# 08_Level_conv_misc.net
KiCad netlist of a schematic drawn in Altium Designer
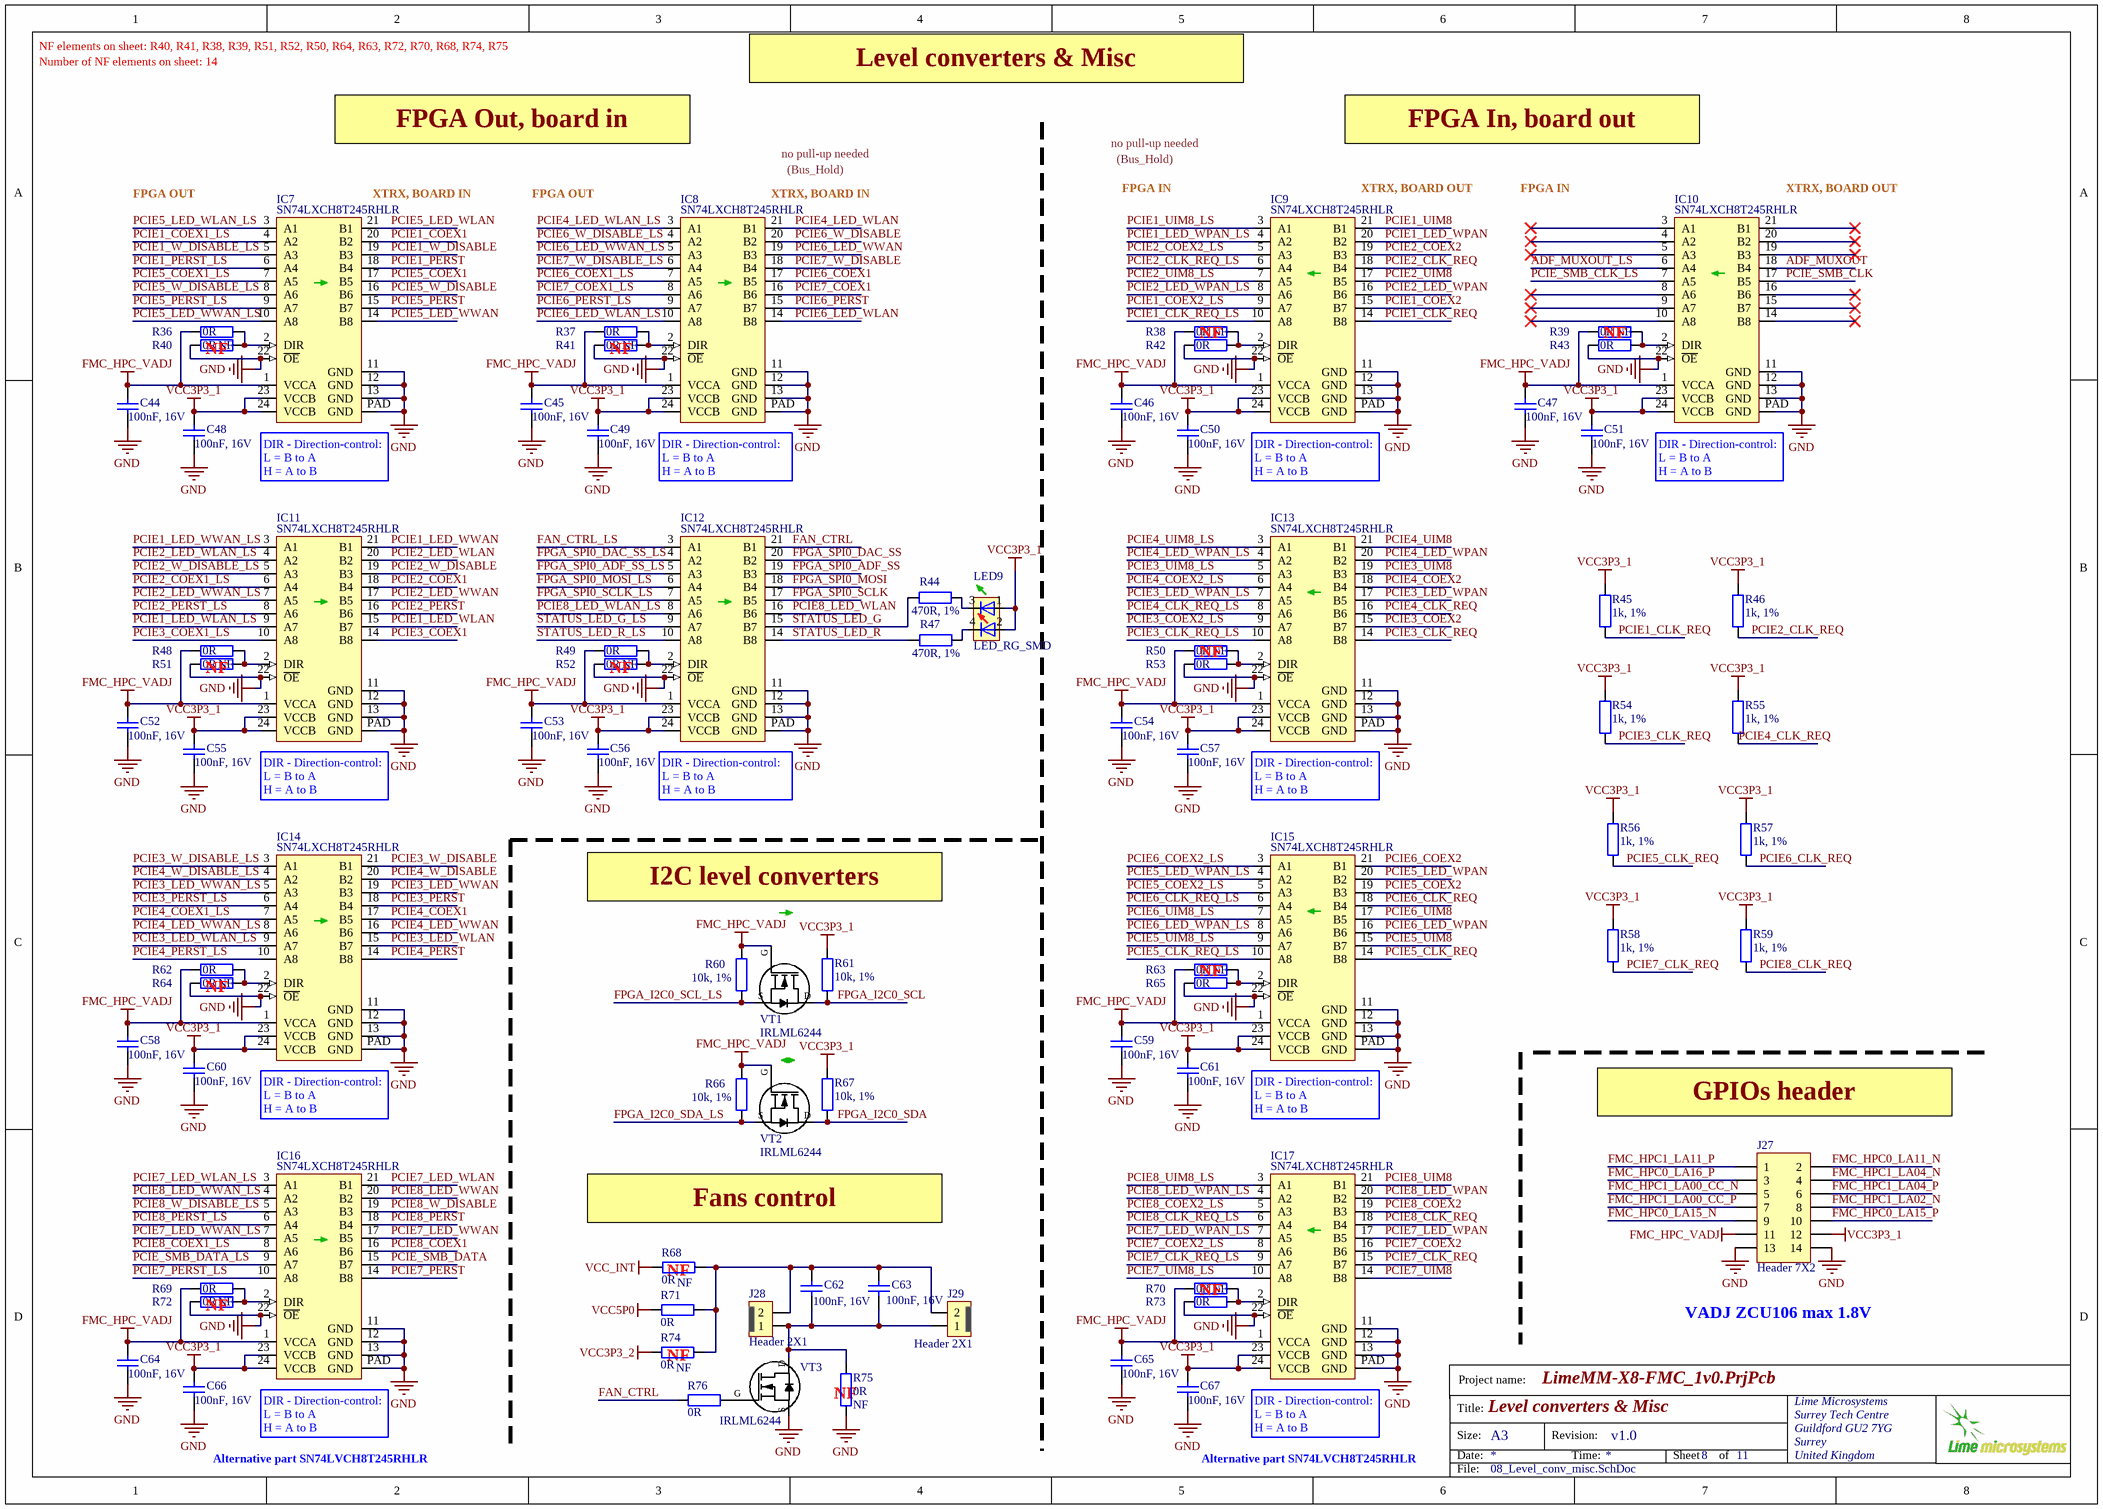
[diagram p0: 08_Level_conv_misc.SchDoc]

(export (version "E")
  (design (tool "Eeschema 10.0.6"))
  (components
    (comp (ref "C44")
      (value "100nF, 16V")
      (footprint "CAP0402")
      (fields (field (name "TOLERANCE") "10 %") (field (name "MANUFACTURER") "Murata Electronics"))
      (libsource (lib "") (part "Cap_0603_1"))
    )
    (comp (ref "C45")
      (value "100nF, 16V")
      (footprint "CAP0402")
      (fields (field (name "TOLERANCE") "10 %") (field (name "MANUFACTURER") "Murata Electronics"))
      (libsource (lib "") (part "Cap_0603_1"))
    )
    (comp (ref "C46")
      (value "100nF, 16V")
      (footprint "CAP0402")
      (fields (field (name "TOLERANCE") "10 %") (field (name "MANUFACTURER") "Murata Electronics"))
      (libsource (lib "") (part "Cap_0603_1"))
    )
    (comp (ref "C47")
      (value "100nF, 16V")
      (footprint "CAP0402")
      (fields (field (name "TOLERANCE") "10 %") (field (name "MANUFACTURER") "Murata Electronics"))
      (libsource (lib "") (part "Cap_0603_1"))
    )
    (comp (ref "C48")
      (value "100nF, 16V")
      (footprint "CAP0402")
      (fields (field (name "TOLERANCE") "10 %") (field (name "MANUFACTURER") "Murata Electronics"))
      (libsource (lib "") (part "Cap_0603_1"))
    )
    (comp (ref "C49")
      (value "100nF, 16V")
      (footprint "CAP0402")
      (fields (field (name "TOLERANCE") "10 %") (field (name "MANUFACTURER") "Murata Electronics"))
      (libsource (lib "") (part "Cap_0603_1"))
    )
    (comp (ref "C50")
      (value "100nF, 16V")
      (footprint "CAP0402")
      (fields (field (name "TOLERANCE") "10 %") (field (name "MANUFACTURER") "Murata Electronics"))
      (libsource (lib "") (part "Cap_0603_1"))
    )
    (comp (ref "C51")
      (value "100nF, 16V")
      (footprint "CAP0402")
      (fields (field (name "TOLERANCE") "10 %") (field (name "MANUFACTURER") "Murata Electronics"))
      (libsource (lib "") (part "Cap_0603_1"))
    )
    (comp (ref "C52")
      (value "100nF, 16V")
      (footprint "CAP0402")
      (fields (field (name "TOLERANCE") "10 %") (field (name "MANUFACTURER") "Murata Electronics"))
      (libsource (lib "") (part "Cap_0603_1"))
    )
    (comp (ref "C53")
      (value "100nF, 16V")
      (footprint "CAP0402")
      (fields (field (name "TOLERANCE") "10 %") (field (name "MANUFACTURER") "Murata Electronics"))
      (libsource (lib "") (part "Cap_0603_1"))
    )
    (comp (ref "C54")
      (value "100nF, 16V")
      (footprint "CAP0402")
      (fields (field (name "TOLERANCE") "10 %") (field (name "MANUFACTURER") "Murata Electronics"))
      (libsource (lib "") (part "Cap_0603_1"))
    )
    (comp (ref "C55")
      (value "100nF, 16V")
      (footprint "CAP0402")
      (fields (field (name "TOLERANCE") "10 %") (field (name "MANUFACTURER") "Murata Electronics"))
      (libsource (lib "") (part "Cap_0603_1"))
    )
    (comp (ref "C56")
      (value "100nF, 16V")
      (footprint "CAP0402")
      (fields (field (name "TOLERANCE") "10 %") (field (name "MANUFACTURER") "Murata Electronics"))
      (libsource (lib "") (part "Cap_0603_1"))
    )
    (comp (ref "C57")
      (value "100nF, 16V")
      (footprint "CAP0402")
      (fields (field (name "TOLERANCE") "10 %") (field (name "MANUFACTURER") "Murata Electronics"))
      (libsource (lib "") (part "Cap_0603_1"))
    )
    (comp (ref "C58")
      (value "100nF, 16V")
      (footprint "CAP0402")
      (fields (field (name "TOLERANCE") "10 %") (field (name "MANUFACTURER") "Murata Electronics"))
      (libsource (lib "") (part "Cap_0603_1"))
    )
    (comp (ref "C59")
      (value "100nF, 16V")
      (footprint "CAP0402")
      (fields (field (name "TOLERANCE") "10 %") (field (name "MANUFACTURER") "Murata Electronics"))
      (libsource (lib "") (part "Cap_0603_1"))
    )
    (comp (ref "C60")
      (value "100nF, 16V")
      (footprint "CAP0402")
      (fields (field (name "TOLERANCE") "10 %") (field (name "MANUFACTURER") "Murata Electronics"))
      (libsource (lib "") (part "Cap_0603_1"))
    )
    (comp (ref "C61")
      (value "100nF, 16V")
      (footprint "CAP0402")
      (fields (field (name "TOLERANCE") "10 %") (field (name "MANUFACTURER") "Murata Electronics"))
      (libsource (lib "") (part "Cap_0603_1"))
    )
    (comp (ref "C62")
      (value "100nF, 16V")
      (footprint "CAP0402")
      (fields
        (field (name "TOLERANCE") "10 %")
        (field (name "MANUFACTURER") "Murata Electronics")
        (field (name "MANUFACTURER PART NUMBER") "GRM155R71C104KA88D")
      )
      (libsource (lib "LimeFPGAboard_schLib") (part "Cap_0603"))
    )
    (comp (ref "C63")
      (value "100nF, 16V")
      (footprint "CAP0402")
      (fields
        (field (name "TOLERANCE") "10 %")
        (field (name "MANUFACTURER") "Murata Electronics")
        (field (name "MANUFACTURER PART NUMBER") "GRM155R71C104KA88D")
      )
      (libsource (lib "LimeFPGAboard_schLib") (part "Cap_0603"))
    )
    (comp (ref "C64")
      (value "100nF, 16V")
      (footprint "CAP0402")
      (fields (field (name "TOLERANCE") "10 %") (field (name "MANUFACTURER") "Murata Electronics"))
      (libsource (lib "") (part "Cap_0603_1"))
    )
    (comp (ref "C65")
      (value "100nF, 16V")
      (footprint "CAP0402")
      (fields (field (name "TOLERANCE") "10 %") (field (name "MANUFACTURER") "Murata Electronics"))
      (libsource (lib "") (part "Cap_0603_1"))
    )
    (comp (ref "C66")
      (value "100nF, 16V")
      (footprint "CAP0402")
      (fields (field (name "TOLERANCE") "10 %") (field (name "MANUFACTURER") "Murata Electronics"))
      (libsource (lib "") (part "Cap_0603_1"))
    )
    (comp (ref "C67")
      (value "100nF, 16V")
      (footprint "CAP0402")
      (fields (field (name "TOLERANCE") "10 %") (field (name "MANUFACTURER") "Murata Electronics"))
      (libsource (lib "") (part "Cap_0603_1"))
    )
    (comp (ref "IC7")
      (value "SN74LXCH8T245RHLR")
      (footprint "SN74LVC8T245RHLR_24-VQFN_LVL_SHIFTER")
      (fields (field (name "MANUFACTURER") "Texas Instruments"))
      (libsource (lib "*") (part "SN74LVC8T245RHLR_LVL_SHIFTER"))
    )
    (comp (ref "IC8")
      (value "SN74LXCH8T245RHLR")
      (footprint "SN74LVC8T245RHLR_24-VQFN_LVL_SHIFTER")
      (fields (field (name "MANUFACTURER") "Texas Instruments"))
      (libsource (lib "*") (part "SN74LVC8T245RHLR_LVL_SHIFTER"))
    )
    (comp (ref "IC9")
      (value "SN74LXCH8T245RHLR")
      (footprint "SN74LVC8T245RHLR_24-VQFN_LVL_SHIFTER")
      (fields (field (name "MANUFACTURER") "Texas Instruments"))
      (libsource (lib "*") (part "SN74LVC8T245RHLR_LVL_SHIFTER"))
    )
    (comp (ref "IC10")
      (value "SN74LXCH8T245RHLR")
      (footprint "SN74LVC8T245RHLR_24-VQFN_LVL_SHIFTER")
      (fields (field (name "MANUFACTURER") "Texas Instruments"))
      (libsource (lib "*") (part "SN74LVC8T245RHLR_LVL_SHIFTER"))
    )
    (comp (ref "IC11")
      (value "SN74LXCH8T245RHLR")
      (footprint "SN74LVC8T245RHLR_24-VQFN_LVL_SHIFTER")
      (fields (field (name "MANUFACTURER") "Texas Instruments"))
      (libsource (lib "*") (part "SN74LVC8T245RHLR_LVL_SHIFTER"))
    )
    (comp (ref "IC12")
      (value "SN74LXCH8T245RHLR")
      (footprint "SN74LVC8T245RHLR_24-VQFN_LVL_SHIFTER")
      (fields (field (name "MANUFACTURER") "Texas Instruments"))
      (libsource (lib "*") (part "SN74LVC8T245RHLR_LVL_SHIFTER"))
    )
    (comp (ref "IC13")
      (value "SN74LXCH8T245RHLR")
      (footprint "SN74LVC8T245RHLR_24-VQFN_LVL_SHIFTER")
      (fields (field (name "MANUFACTURER") "Texas Instruments"))
      (libsource (lib "*") (part "SN74LVC8T245RHLR_LVL_SHIFTER"))
    )
    (comp (ref "IC14")
      (value "SN74LXCH8T245RHLR")
      (footprint "SN74LVC8T245RHLR_24-VQFN_LVL_SHIFTER")
      (fields (field (name "MANUFACTURER") "Texas Instruments"))
      (libsource (lib "*") (part "SN74LVC8T245RHLR_LVL_SHIFTER"))
    )
    (comp (ref "IC15")
      (value "SN74LXCH8T245RHLR")
      (footprint "SN74LVC8T245RHLR_24-VQFN_LVL_SHIFTER")
      (fields (field (name "MANUFACTURER") "Texas Instruments"))
      (libsource (lib "*") (part "SN74LVC8T245RHLR_LVL_SHIFTER"))
    )
    (comp (ref "IC16")
      (value "SN74LXCH8T245RHLR")
      (footprint "SN74LVC8T245RHLR_24-VQFN_LVL_SHIFTER")
      (fields (field (name "MANUFACTURER") "Texas Instruments"))
      (libsource (lib "*") (part "SN74LVC8T245RHLR_LVL_SHIFTER"))
    )
    (comp (ref "IC17")
      (value "SN74LXCH8T245RHLR")
      (footprint "SN74LVC8T245RHLR_24-VQFN_LVL_SHIFTER")
      (fields (field (name "MANUFACTURER") "Texas Instruments"))
      (libsource (lib "*") (part "SN74LVC8T245RHLR_LVL_SHIFTER"))
    )
    (comp (ref "J27")
      (value "Header 7X2")
      (footprint "Header7x2_TH")
      (description "Header, 7-Pin, Dual row")
      (fields
        (field (name "MANUFACTURER PART NUMBER") "PH2-14-UA")
        (field (name "MANUFACTURER") "Adam Equipment")
      )
      (libsource (lib "LimeMicroAltiumLib_schLib_r04") (part "Header 7X2"))
    )
    (comp (ref "J28")
      (value "Header 2X1")
      (footprint "Header1x2_TH_LOCKING")
      (fields (field (name "MANUFACTURER PART NUMBER") "22-11-2026") (field (name "MANUFACTURER") "Molex"))
      (libsource (lib "") (part "Header 2X1 LOCK_1"))
    )
    (comp (ref "J29")
      (value "Header 2X1")
      (footprint "Header1x2_TH_LOCKING")
      (fields (field (name "MANUFACTURER PART NUMBER") "22-11-2026") (field (name "MANUFACTURER") "Molex"))
      (libsource (lib "LimeMicroAltiumLib_schLib_r04") (part "Header 2X1 LOCK"))
    )
    (comp (ref "LED9")
      (value "LED_RG_SMD")
      (footprint "LED-2x0603")
      (fields (field (name "MANUFACTURER") "Avago Technologies US Inc."))
      (libsource (lib "LimeMicroAltiumLib_schLib") (part "LED_green_red_SMD"))
    )
    (comp (ref "R36")
      (value "0R")
      (footprint "RES0402")
      (fields (field (name "MANUFACTURER") "Yageo") (field (name "TOLERANCE") "Jumper"))
      (libsource (lib "LimeMicroAltiumLib_schLib") (part "Res_0402"))
    )
    (comp (ref "R37")
      (value "0R")
      (footprint "RES0402")
      (fields (field (name "MANUFACTURER") "Yageo") (field (name "TOLERANCE") "Jumper"))
      (libsource (lib "LimeMicroAltiumLib_schLib") (part "Res_0402"))
    )
    (comp (ref "R38")
      (value "0R")
      (footprint "RES0402")
      (fields
        (field (name "ASSEMBLY INFO") "NF")
        (field (name "MANUFACTURER") "Yageo")
        (field (name "TOLERANCE") "Jumper")
      )
      (libsource (lib "LimeMicroAltiumLib_schLib") (part "Res_0402"))
    )
    (comp (ref "R39")
      (value "0R")
      (footprint "RES0402")
      (fields
        (field (name "ASSEMBLY INFO") "NF")
        (field (name "MANUFACTURER") "Yageo")
        (field (name "TOLERANCE") "Jumper")
      )
      (libsource (lib "LimeMicroAltiumLib_schLib") (part "Res_0402"))
    )
    (comp (ref "R40")
      (value "0R")
      (footprint "RES0402")
      (fields
        (field (name "ASSEMBLY INFO") "NF")
        (field (name "MANUFACTURER") "Yageo")
        (field (name "TOLERANCE") "Jumper")
      )
      (libsource (lib "LimeMicroAltiumLib_schLib") (part "Res_0402"))
    )
    (comp (ref "R41")
      (value "0R")
      (footprint "RES0402")
      (fields
        (field (name "ASSEMBLY INFO") "NF")
        (field (name "MANUFACTURER") "Yageo")
        (field (name "TOLERANCE") "Jumper")
      )
      (libsource (lib "LimeMicroAltiumLib_schLib") (part "Res_0402"))
    )
    (comp (ref "R42")
      (value "0R")
      (footprint "RES0402")
      (fields (field (name "MANUFACTURER") "Yageo") (field (name "TOLERANCE") "Jumper"))
      (libsource (lib "LimeMicroAltiumLib_schLib") (part "Res_0402"))
    )
    (comp (ref "R43")
      (value "0R")
      (footprint "RES0402")
      (fields (field (name "MANUFACTURER") "Yageo") (field (name "TOLERANCE") "Jumper"))
      (libsource (lib "LimeMicroAltiumLib_schLib") (part "Res_0402"))
    )
    (comp (ref "R44")
      (value "470R, 1%")
      (footprint "RES0402")
      (fields (field (name "TOLERANCE") "1%") (field (name "MANUFACTURER") "Yageo"))
      (libsource (lib "LimeMicroAltiumLib_schLib") (part "Res_0402"))
    )
    (comp (ref "R45")
      (value "1k, 1%")
      (footprint "RES0402")
      (fields (field (name "MANUFACTURER") "Stackpole Electronics Inc") (field (name "TOLERANCE") "±1%"))
      (libsource (lib "") (part "Res_0402_1"))
    )
    (comp (ref "R46")
      (value "1k, 1%")
      (footprint "RES0402")
      (fields (field (name "MANUFACTURER") "Stackpole Electronics Inc") (field (name "TOLERANCE") "±1%"))
      (libsource (lib "") (part "Res_0402_1"))
    )
    (comp (ref "R47")
      (value "470R, 1%")
      (footprint "RES0402")
      (fields (field (name "TOLERANCE") "1%") (field (name "MANUFACTURER") "Yageo"))
      (libsource (lib "LimeMicroAltiumLib_schLib") (part "Res_0402"))
    )
    (comp (ref "R48")
      (value "0R")
      (footprint "RES0402")
      (fields (field (name "MANUFACTURER") "Yageo") (field (name "TOLERANCE") "Jumper"))
      (libsource (lib "LimeMicroAltiumLib_schLib") (part "Res_0402"))
    )
    (comp (ref "R49")
      (value "0R")
      (footprint "RES0402")
      (fields (field (name "MANUFACTURER") "Yageo") (field (name "TOLERANCE") "Jumper"))
      (libsource (lib "LimeMicroAltiumLib_schLib") (part "Res_0402"))
    )
    (comp (ref "R50")
      (value "0R")
      (footprint "RES0402")
      (fields
        (field (name "ASSEMBLY INFO") "NF")
        (field (name "MANUFACTURER") "Yageo")
        (field (name "TOLERANCE") "Jumper")
      )
      (libsource (lib "LimeMicroAltiumLib_schLib") (part "Res_0402"))
    )
    (comp (ref "R51")
      (value "0R")
      (footprint "RES0402")
      (fields
        (field (name "ASSEMBLY INFO") "NF")
        (field (name "MANUFACTURER") "Yageo")
        (field (name "TOLERANCE") "Jumper")
      )
      (libsource (lib "LimeMicroAltiumLib_schLib") (part "Res_0402"))
    )
    (comp (ref "R52")
      (value "0R")
      (footprint "RES0402")
      (fields
        (field (name "ASSEMBLY INFO") "NF")
        (field (name "MANUFACTURER") "Yageo")
        (field (name "TOLERANCE") "Jumper")
      )
      (libsource (lib "LimeMicroAltiumLib_schLib") (part "Res_0402"))
    )
    (comp (ref "R53")
      (value "0R")
      (footprint "RES0402")
      (fields (field (name "MANUFACTURER") "Yageo") (field (name "TOLERANCE") "Jumper"))
      (libsource (lib "LimeMicroAltiumLib_schLib") (part "Res_0402"))
    )
    (comp (ref "R54")
      (value "1k, 1%")
      (footprint "RES0402")
      (fields (field (name "MANUFACTURER") "Stackpole Electronics Inc") (field (name "TOLERANCE") "±1%"))
      (libsource (lib "") (part "Res_0402_1"))
    )
    (comp (ref "R55")
      (value "1k, 1%")
      (footprint "RES0402")
      (fields (field (name "MANUFACTURER") "Stackpole Electronics Inc") (field (name "TOLERANCE") "±1%"))
      (libsource (lib "") (part "Res_0402_1"))
    )
    (comp (ref "R56")
      (value "1k, 1%")
      (footprint "RES0402")
      (fields (field (name "MANUFACTURER") "Stackpole Electronics Inc") (field (name "TOLERANCE") "±1%"))
      (libsource (lib "") (part "Res_0402_1"))
    )
    (comp (ref "R57")
      (value "1k, 1%")
      (footprint "RES0402")
      (fields (field (name "MANUFACTURER") "Stackpole Electronics Inc") (field (name "TOLERANCE") "±1%"))
      (libsource (lib "") (part "Res_0402_1"))
    )
    (comp (ref "R58")
      (value "1k, 1%")
      (footprint "RES0402")
      (fields (field (name "MANUFACTURER") "Stackpole Electronics Inc") (field (name "TOLERANCE") "±1%"))
      (libsource (lib "") (part "Res_0402_1"))
    )
    (comp (ref "R59")
      (value "1k, 1%")
      (footprint "RES0402")
      (fields (field (name "MANUFACTURER") "Stackpole Electronics Inc") (field (name "TOLERANCE") "±1%"))
      (libsource (lib "") (part "Res_0402_1"))
    )
    (comp (ref "R60")
      (value "10k, 1%")
      (footprint "RES0402")
      (fields (field (name "MANUFACTURER") "Yageo") (field (name "TOLERANCE") "±1%"))
      (libsource (lib "") (part "Res_0402_1"))
    )
    (comp (ref "R61")
      (value "10k, 1%")
      (footprint "RES0402")
      (fields (field (name "MANUFACTURER") "Yageo") (field (name "TOLERANCE") "±1%"))
      (libsource (lib "") (part "Res_0402_1"))
    )
    (comp (ref "R62")
      (value "0R")
      (footprint "RES0402")
      (fields (field (name "MANUFACTURER") "Yageo") (field (name "TOLERANCE") "Jumper"))
      (libsource (lib "LimeMicroAltiumLib_schLib") (part "Res_0402"))
    )
    (comp (ref "R63")
      (value "0R")
      (footprint "RES0402")
      (fields
        (field (name "ASSEMBLY INFO") "NF")
        (field (name "MANUFACTURER") "Yageo")
        (field (name "TOLERANCE") "Jumper")
      )
      (libsource (lib "LimeMicroAltiumLib_schLib") (part "Res_0402"))
    )
    (comp (ref "R64")
      (value "0R")
      (footprint "RES0402")
      (fields
        (field (name "ASSEMBLY INFO") "NF")
        (field (name "MANUFACTURER") "Yageo")
        (field (name "TOLERANCE") "Jumper")
      )
      (libsource (lib "LimeMicroAltiumLib_schLib") (part "Res_0402"))
    )
    (comp (ref "R65")
      (value "0R")
      (footprint "RES0402")
      (fields (field (name "MANUFACTURER") "Yageo") (field (name "TOLERANCE") "Jumper"))
      (libsource (lib "LimeMicroAltiumLib_schLib") (part "Res_0402"))
    )
    (comp (ref "R66")
      (value "10k, 1%")
      (footprint "RES0402")
      (fields (field (name "MANUFACTURER") "Yageo") (field (name "TOLERANCE") "±1%"))
      (libsource (lib "") (part "Res_0402_1"))
    )
    (comp (ref "R67")
      (value "10k, 1%")
      (footprint "RES0402")
      (fields (field (name "MANUFACTURER") "Yageo") (field (name "TOLERANCE") "±1%"))
      (libsource (lib "") (part "Res_0402_1"))
    )
    (comp (ref "R68")
      (value "0R")
      (footprint "RES0402")
      (fields
        (field (name "ASSEMBLY INFO") "NF")
        (field (name "MANUFACTURER") "Yageo")
        (field (name "TOLERANCE") "Jumper")
      )
      (libsource (lib "") (part "Res_0402_1"))
    )
    (comp (ref "R69")
      (value "0R")
      (footprint "RES0402")
      (fields (field (name "MANUFACTURER") "Yageo") (field (name "TOLERANCE") "Jumper"))
      (libsource (lib "LimeMicroAltiumLib_schLib") (part "Res_0402"))
    )
    (comp (ref "R70")
      (value "0R")
      (footprint "RES0402")
      (fields
        (field (name "ASSEMBLY INFO") "NF")
        (field (name "MANUFACTURER") "Yageo")
        (field (name "TOLERANCE") "Jumper")
      )
      (libsource (lib "LimeMicroAltiumLib_schLib") (part "Res_0402"))
    )
    (comp (ref "R71")
      (value "0R")
      (footprint "RES0402")
      (fields (field (name "MANUFACTURER") "Yageo") (field (name "TOLERANCE") "Jumper"))
      (libsource (lib "") (part "Res_0402_1"))
    )
    (comp (ref "R72")
      (value "0R")
      (footprint "RES0402")
      (fields
        (field (name "ASSEMBLY INFO") "NF")
        (field (name "MANUFACTURER") "Yageo")
        (field (name "TOLERANCE") "Jumper")
      )
      (libsource (lib "LimeMicroAltiumLib_schLib") (part "Res_0402"))
    )
    (comp (ref "R73")
      (value "0R")
      (footprint "RES0402")
      (fields (field (name "MANUFACTURER") "Yageo") (field (name "TOLERANCE") "Jumper"))
      (libsource (lib "LimeMicroAltiumLib_schLib") (part "Res_0402"))
    )
    (comp (ref "R74")
      (value "0R")
      (footprint "RES0402")
      (fields
        (field (name "ASSEMBLY INFO") "NF")
        (field (name "MANUFACTURER") "Yageo")
        (field (name "TOLERANCE") "Jumper")
      )
      (libsource (lib "") (part "Res_0402_1"))
    )
    (comp (ref "R75")
      (value "0R")
      (footprint "RES0402")
      (fields
        (field (name "ASSEMBLY INFO") "NF")
        (field (name "MANUFACTURER") "Yageo")
        (field (name "TOLERANCE") "Jumper")
      )
      (libsource (lib "") (part "Res_0402_1"))
    )
    (comp (ref "R76")
      (value "0R")
      (footprint "RES0402")
      (fields (field (name "MANUFACTURER") "Yageo") (field (name "TOLERANCE") "Jumper"))
      (libsource (lib "") (part "Res_0402_1"))
    )
    (comp (ref "VT1")
      (value "IRLML6244")
      (footprint "SOT23-3")
      (description "NDS331N")
      (fields (field (name "MANUFACTURER") "Infineon Technologies"))
      (libsource (lib "LimeFPGAboard_schLib") (part "NDS331N"))
    )
    (comp (ref "VT2")
      (value "IRLML6244")
      (footprint "SOT23-3")
      (description "NDS331N")
      (fields (field (name "MANUFACTURER") "Infineon Technologies"))
      (libsource (lib "LimeFPGAboard_schLib") (part "NDS331N"))
    )
    (comp (ref "VT3")
      (value "IRLML6244")
      (footprint "SOT23-3")
      (description "NDS331N")
      (fields (field (name "MANUFACTURER") "Infineon Technologies"))
      (libsource (lib "LimeFPGAboard_schLib") (part "NDS331N"))
    )
  )
  (nets
    (net (code "1") (name "/ADF_MUXOUT") (class "Default")
      (node (ref "IC10") (pin "18") (pinfunction "B4_18") (pintype "bidirectional"))
    )
    (net (code "2") (name "/ADF_MUXOUT_LS") (class "Default")
      (node (ref "IC10") (pin "6") (pinfunction "A4_6") (pintype "bidirectional"))
    )
    (net (code "3") (name "/FAN_CTRL") (class "Default")
      (node (ref "IC12") (pin "21") (pinfunction "B1_21") (pintype "bidirectional"))
      (node (ref "R76") (pin "1") (pinfunction "1_1") (pintype "passive"))
    )
    (net (code "4") (name "/FAN_CTRL_LS") (class "Default")
      (node (ref "IC12") (pin "3") (pinfunction "A1_3") (pintype "bidirectional"))
    )
    (net (code "5") (name "/FMC_HPC0_LA11_N") (class "Default")
      (node (ref "J27") (pin "2") (pinfunction "2_2") (pintype "passive"))
    )
    (net (code "6") (name "/FMC_HPC0_LA15_N") (class "Default")
      (node (ref "J27") (pin "9") (pinfunction "9_9") (pintype "passive"))
    )
    (net (code "7") (name "/FMC_HPC0_LA15_P") (class "Default")
      (node (ref "J27") (pin "10") (pinfunction "10_10") (pintype "passive"))
    )
    (net (code "8") (name "/FMC_HPC0_LA16_P") (class "Default")
      (node (ref "J27") (pin "3") (pinfunction "3_3") (pintype "passive"))
    )
    (net (code "9") (name "/FMC_HPC1_LA00_CC_N") (class "Default")
      (node (ref "J27") (pin "5") (pinfunction "5_5") (pintype "passive"))
    )
    (net (code "10") (name "/FMC_HPC1_LA00_CC_P") (class "Default")
      (node (ref "J27") (pin "7") (pinfunction "7_7") (pintype "passive"))
    )
    (net (code "11") (name "/FMC_HPC1_LA02_N") (class "Default")
      (node (ref "J27") (pin "8") (pinfunction "8_8") (pintype "passive"))
    )
    (net (code "12") (name "/FMC_HPC1_LA04_N") (class "Default")
      (node (ref "J27") (pin "4") (pinfunction "4_4") (pintype "passive"))
    )
    (net (code "13") (name "/FMC_HPC1_LA04_P") (class "Default")
      (node (ref "J27") (pin "6") (pinfunction "6_6") (pintype "passive"))
    )
    (net (code "14") (name "/FMC_HPC1_LA11_P") (class "Default")
      (node (ref "J27") (pin "1") (pinfunction "1_1") (pintype "passive"))
    )
    (net (code "15") (name "/FPGA_I2C0_SCL") (class "Default")
      (node (ref "R61") (pin "2") (pinfunction "2_2") (pintype "passive"))
      (node (ref "VT1") (pin "D") (pinfunction "D_D") (pintype "passive"))
    )
    (net (code "16") (name "/FPGA_I2C0_SCL_LS") (class "Default")
      (node (ref "R60") (pin "2") (pinfunction "2_2") (pintype "passive"))
      (node (ref "VT1") (pin "S") (pinfunction "S_S") (pintype "passive"))
    )
    (net (code "17") (name "/FPGA_I2C0_SDA") (class "Default")
      (node (ref "R67") (pin "2") (pinfunction "2_2") (pintype "passive"))
      (node (ref "VT2") (pin "D") (pinfunction "D_D") (pintype "passive"))
    )
    (net (code "18") (name "/FPGA_I2C0_SDA_LS") (class "Default")
      (node (ref "R66") (pin "2") (pinfunction "2_2") (pintype "passive"))
      (node (ref "VT2") (pin "S") (pinfunction "S_S") (pintype "passive"))
    )
    (net (code "19") (name "/FPGA_SPI0_ADF_SS") (class "Default")
      (node (ref "IC12") (pin "19") (pinfunction "B3_19") (pintype "bidirectional"))
    )
    (net (code "20") (name "/FPGA_SPI0_ADF_SS_LS") (class "Default")
      (node (ref "IC12") (pin "5") (pinfunction "A3_5") (pintype "bidirectional"))
    )
    (net (code "21") (name "/FPGA_SPI0_DAC_SS") (class "Default")
      (node (ref "IC12") (pin "20") (pinfunction "B2_20") (pintype "bidirectional"))
    )
    (net (code "22") (name "/FPGA_SPI0_DAC_SS_LS") (class "Default")
      (node (ref "IC12") (pin "4") (pinfunction "A2_4") (pintype "bidirectional"))
    )
    (net (code "23") (name "/FPGA_SPI0_MOSI") (class "Default")
      (node (ref "IC12") (pin "18") (pinfunction "B4_18") (pintype "bidirectional"))
    )
    (net (code "24") (name "/FPGA_SPI0_MOSI_LS") (class "Default")
      (node (ref "IC12") (pin "6") (pinfunction "A4_6") (pintype "bidirectional"))
    )
    (net (code "25") (name "/FPGA_SPI0_SCLK") (class "Default")
      (node (ref "IC12") (pin "17") (pinfunction "B5_17") (pintype "bidirectional"))
    )
    (net (code "26") (name "/FPGA_SPI0_SCLK_LS") (class "Default")
      (node (ref "IC12") (pin "7") (pinfunction "A5_7") (pintype "bidirectional"))
    )
    (net (code "27") (name "/PCIE1_CLK_REQ") (class "Default")
      (node (ref "IC9") (pin "14") (pinfunction "B8_14") (pintype "bidirectional"))
      (node (ref "R45") (pin "1") (pinfunction "1_1") (pintype "passive"))
    )
    (net (code "28") (name "/PCIE1_CLK_REQ_LS") (class "Default")
      (node (ref "IC9") (pin "10") (pinfunction "A8_10") (pintype "bidirectional"))
    )
    (net (code "29") (name "/PCIE1_COEX1") (class "Default")
      (node (ref "IC7") (pin "20") (pinfunction "B2_20") (pintype "bidirectional"))
    )
    (net (code "30") (name "/PCIE1_COEX1_LS") (class "Default")
      (node (ref "IC7") (pin "4") (pinfunction "A2_4") (pintype "bidirectional"))
    )
    (net (code "31") (name "/PCIE1_COEX2") (class "Default")
      (node (ref "IC9") (pin "15") (pinfunction "B7_15") (pintype "bidirectional"))
    )
    (net (code "32") (name "/PCIE1_COEX2_LS") (class "Default")
      (node (ref "IC9") (pin "9") (pinfunction "A7_9") (pintype "bidirectional"))
    )
    (net (code "33") (name "/PCIE1_LED_WLAN") (class "Default")
      (node (ref "IC11") (pin "15") (pinfunction "B7_15") (pintype "bidirectional"))
    )
    (net (code "34") (name "/PCIE1_LED_WLAN_LS") (class "Default")
      (node (ref "IC11") (pin "9") (pinfunction "A7_9") (pintype "bidirectional"))
    )
    (net (code "35") (name "/PCIE1_LED_WPAN") (class "Default")
      (node (ref "IC9") (pin "20") (pinfunction "B2_20") (pintype "bidirectional"))
    )
    (net (code "36") (name "/PCIE1_LED_WPAN_LS") (class "Default")
      (node (ref "IC9") (pin "4") (pinfunction "A2_4") (pintype "bidirectional"))
    )
    (net (code "37") (name "/PCIE1_LED_WWAN") (class "Default")
      (node (ref "IC11") (pin "21") (pinfunction "B1_21") (pintype "bidirectional"))
    )
    (net (code "38") (name "/PCIE1_LED_WWAN_LS") (class "Default")
      (node (ref "IC11") (pin "3") (pinfunction "A1_3") (pintype "bidirectional"))
    )
    (net (code "39") (name "/PCIE1_PERST") (class "Default")
      (node (ref "IC7") (pin "18") (pinfunction "B4_18") (pintype "bidirectional"))
    )
    (net (code "40") (name "/PCIE1_PERST_LS") (class "Default")
      (node (ref "IC7") (pin "6") (pinfunction "A4_6") (pintype "bidirectional"))
    )
    (net (code "41") (name "/PCIE1_UIM8") (class "Default")
      (node (ref "IC9") (pin "21") (pinfunction "B1_21") (pintype "bidirectional"))
    )
    (net (code "42") (name "/PCIE1_UIM8_LS") (class "Default")
      (node (ref "IC9") (pin "3") (pinfunction "A1_3") (pintype "bidirectional"))
    )
    (net (code "43") (name "/PCIE1_W_DISABLE") (class "Default")
      (node (ref "IC7") (pin "19") (pinfunction "B3_19") (pintype "bidirectional"))
    )
    (net (code "44") (name "/PCIE1_W_DISABLE_LS") (class "Default")
      (node (ref "IC7") (pin "5") (pinfunction "A3_5") (pintype "bidirectional"))
    )
    (net (code "45") (name "/PCIE2_CLK_REQ") (class "Default")
      (node (ref "IC9") (pin "18") (pinfunction "B4_18") (pintype "bidirectional"))
      (node (ref "R46") (pin "1") (pinfunction "1_1") (pintype "passive"))
    )
    (net (code "46") (name "/PCIE2_CLK_REQ_LS") (class "Default")
      (node (ref "IC9") (pin "6") (pinfunction "A4_6") (pintype "bidirectional"))
    )
    (net (code "47") (name "/PCIE2_COEX1") (class "Default")
      (node (ref "IC11") (pin "18") (pinfunction "B4_18") (pintype "bidirectional"))
    )
    (net (code "48") (name "/PCIE2_COEX1_LS") (class "Default")
      (node (ref "IC11") (pin "6") (pinfunction "A4_6") (pintype "bidirectional"))
    )
    (net (code "49") (name "/PCIE2_COEX2") (class "Default")
      (node (ref "IC9") (pin "19") (pinfunction "B3_19") (pintype "bidirectional"))
    )
    (net (code "50") (name "/PCIE2_COEX2_LS") (class "Default")
      (node (ref "IC9") (pin "5") (pinfunction "A3_5") (pintype "bidirectional"))
    )
    (net (code "51") (name "/PCIE2_LED_WLAN") (class "Default")
      (node (ref "IC11") (pin "20") (pinfunction "B2_20") (pintype "bidirectional"))
    )
    (net (code "52") (name "/PCIE2_LED_WLAN_LS") (class "Default")
      (node (ref "IC11") (pin "4") (pinfunction "A2_4") (pintype "bidirectional"))
    )
    (net (code "53") (name "/PCIE2_LED_WPAN") (class "Default")
      (node (ref "IC9") (pin "16") (pinfunction "B6_16") (pintype "bidirectional"))
    )
    (net (code "54") (name "/PCIE2_LED_WPAN_LS") (class "Default")
      (node (ref "IC9") (pin "8") (pinfunction "A6_8") (pintype "bidirectional"))
    )
    (net (code "55") (name "/PCIE2_LED_WWAN") (class "Default")
      (node (ref "IC11") (pin "17") (pinfunction "B5_17") (pintype "bidirectional"))
    )
    (net (code "56") (name "/PCIE2_LED_WWAN_LS") (class "Default")
      (node (ref "IC11") (pin "7") (pinfunction "A5_7") (pintype "bidirectional"))
    )
    (net (code "57") (name "/PCIE2_PERST") (class "Default")
      (node (ref "IC11") (pin "16") (pinfunction "B6_16") (pintype "bidirectional"))
    )
    (net (code "58") (name "/PCIE2_PERST_LS") (class "Default")
      (node (ref "IC11") (pin "8") (pinfunction "A6_8") (pintype "bidirectional"))
    )
    (net (code "59") (name "/PCIE2_UIM8") (class "Default")
      (node (ref "IC9") (pin "17") (pinfunction "B5_17") (pintype "bidirectional"))
    )
    (net (code "60") (name "/PCIE2_UIM8_LS") (class "Default")
      (node (ref "IC9") (pin "7") (pinfunction "A5_7") (pintype "bidirectional"))
    )
    (net (code "61") (name "/PCIE2_W_DISABLE") (class "Default")
      (node (ref "IC11") (pin "19") (pinfunction "B3_19") (pintype "bidirectional"))
    )
    (net (code "62") (name "/PCIE2_W_DISABLE_LS") (class "Default")
      (node (ref "IC11") (pin "5") (pinfunction "A3_5") (pintype "bidirectional"))
    )
    (net (code "63") (name "/PCIE3_CLK_REQ") (class "Default")
      (node (ref "IC13") (pin "14") (pinfunction "B8_14") (pintype "bidirectional"))
      (node (ref "R54") (pin "1") (pinfunction "1_1") (pintype "passive"))
    )
    (net (code "64") (name "/PCIE3_CLK_REQ_LS") (class "Default")
      (node (ref "IC13") (pin "10") (pinfunction "A8_10") (pintype "bidirectional"))
    )
    (net (code "65") (name "/PCIE3_COEX1") (class "Default")
      (node (ref "IC11") (pin "14") (pinfunction "B8_14") (pintype "bidirectional"))
    )
    (net (code "66") (name "/PCIE3_COEX1_LS") (class "Default")
      (node (ref "IC11") (pin "10") (pinfunction "A8_10") (pintype "bidirectional"))
    )
    (net (code "67") (name "/PCIE3_COEX2") (class "Default")
      (node (ref "IC13") (pin "15") (pinfunction "B7_15") (pintype "bidirectional"))
    )
    (net (code "68") (name "/PCIE3_COEX2_LS") (class "Default")
      (node (ref "IC13") (pin "9") (pinfunction "A7_9") (pintype "bidirectional"))
    )
    (net (code "69") (name "/PCIE3_LED_WLAN") (class "Default")
      (node (ref "IC14") (pin "15") (pinfunction "B7_15") (pintype "bidirectional"))
    )
    (net (code "70") (name "/PCIE3_LED_WLAN_LS") (class "Default")
      (node (ref "IC14") (pin "9") (pinfunction "A7_9") (pintype "bidirectional"))
    )
    (net (code "71") (name "/PCIE3_LED_WPAN") (class "Default")
      (node (ref "IC13") (pin "17") (pinfunction "B5_17") (pintype "bidirectional"))
    )
    (net (code "72") (name "/PCIE3_LED_WPAN_LS") (class "Default")
      (node (ref "IC13") (pin "7") (pinfunction "A5_7") (pintype "bidirectional"))
    )
    (net (code "73") (name "/PCIE3_LED_WWAN") (class "Default")
      (node (ref "IC14") (pin "19") (pinfunction "B3_19") (pintype "bidirectional"))
    )
    (net (code "74") (name "/PCIE3_LED_WWAN_LS") (class "Default")
      (node (ref "IC14") (pin "5") (pinfunction "A3_5") (pintype "bidirectional"))
    )
    (net (code "75") (name "/PCIE3_PERST") (class "Default")
      (node (ref "IC14") (pin "18") (pinfunction "B4_18") (pintype "bidirectional"))
    )
    (net (code "76") (name "/PCIE3_PERST_LS") (class "Default")
      (node (ref "IC14") (pin "6") (pinfunction "A4_6") (pintype "bidirectional"))
    )
    (net (code "77") (name "/PCIE3_UIM8") (class "Default")
      (node (ref "IC13") (pin "19") (pinfunction "B3_19") (pintype "bidirectional"))
    )
    (net (code "78") (name "/PCIE3_UIM8_LS") (class "Default")
      (node (ref "IC13") (pin "5") (pinfunction "A3_5") (pintype "bidirectional"))
    )
    (net (code "79") (name "/PCIE3_W_DISABLE") (class "Default")
      (node (ref "IC14") (pin "21") (pinfunction "B1_21") (pintype "bidirectional"))
    )
    (net (code "80") (name "/PCIE3_W_DISABLE_LS") (class "Default")
      (node (ref "IC14") (pin "3") (pinfunction "A1_3") (pintype "bidirectional"))
    )
    (net (code "81") (name "/PCIE4_CLK_REQ") (class "Default")
      (node (ref "IC13") (pin "16") (pinfunction "B6_16") (pintype "bidirectional"))
      (node (ref "R55") (pin "1") (pinfunction "1_1") (pintype "passive"))
    )
    (net (code "82") (name "/PCIE4_CLK_REQ_LS") (class "Default")
      (node (ref "IC13") (pin "8") (pinfunction "A6_8") (pintype "bidirectional"))
    )
    (net (code "83") (name "/PCIE4_COEX1") (class "Default")
      (node (ref "IC14") (pin "17") (pinfunction "B5_17") (pintype "bidirectional"))
    )
    (net (code "84") (name "/PCIE4_COEX1_LS") (class "Default")
      (node (ref "IC14") (pin "7") (pinfunction "A5_7") (pintype "bidirectional"))
    )
    (net (code "85") (name "/PCIE4_COEX2") (class "Default")
      (node (ref "IC13") (pin "18") (pinfunction "B4_18") (pintype "bidirectional"))
    )
    (net (code "86") (name "/PCIE4_COEX2_LS") (class "Default")
      (node (ref "IC13") (pin "6") (pinfunction "A4_6") (pintype "bidirectional"))
    )
    (net (code "87") (name "/PCIE4_LED_WLAN") (class "Default")
      (node (ref "IC8") (pin "21") (pinfunction "B1_21") (pintype "bidirectional"))
    )
    (net (code "88") (name "/PCIE4_LED_WLAN_LS") (class "Default")
      (node (ref "IC8") (pin "3") (pinfunction "A1_3") (pintype "bidirectional"))
    )
    (net (code "89") (name "/PCIE4_LED_WPAN") (class "Default")
      (node (ref "IC13") (pin "20") (pinfunction "B2_20") (pintype "bidirectional"))
    )
    (net (code "90") (name "/PCIE4_LED_WPAN_LS") (class "Default")
      (node (ref "IC13") (pin "4") (pinfunction "A2_4") (pintype "bidirectional"))
    )
    (net (code "91") (name "/PCIE4_LED_WWAN") (class "Default")
      (node (ref "IC14") (pin "16") (pinfunction "B6_16") (pintype "bidirectional"))
    )
    (net (code "92") (name "/PCIE4_LED_WWAN_LS") (class "Default")
      (node (ref "IC14") (pin "8") (pinfunction "A6_8") (pintype "bidirectional"))
    )
    (net (code "93") (name "/PCIE4_PERST") (class "Default")
      (node (ref "IC14") (pin "14") (pinfunction "B8_14") (pintype "bidirectional"))
    )
    (net (code "94") (name "/PCIE4_PERST_LS") (class "Default")
      (node (ref "IC14") (pin "10") (pinfunction "A8_10") (pintype "bidirectional"))
    )
    (net (code "95") (name "/PCIE4_UIM8") (class "Default")
      (node (ref "IC13") (pin "21") (pinfunction "B1_21") (pintype "bidirectional"))
    )
    (net (code "96") (name "/PCIE4_UIM8_LS") (class "Default")
      (node (ref "IC13") (pin "3") (pinfunction "A1_3") (pintype "bidirectional"))
    )
    (net (code "97") (name "/PCIE4_W_DISABLE") (class "Default")
      (node (ref "IC14") (pin "20") (pinfunction "B2_20") (pintype "bidirectional"))
    )
    (net (code "98") (name "/PCIE4_W_DISABLE_LS") (class "Default")
      (node (ref "IC14") (pin "4") (pinfunction "A2_4") (pintype "bidirectional"))
    )
    (net (code "99") (name "/PCIE5_CLK_REQ") (class "Default")
      (node (ref "IC15") (pin "14") (pinfunction "B8_14") (pintype "bidirectional"))
      (node (ref "R56") (pin "1") (pinfunction "1_1") (pintype "passive"))
    )
    (net (code "100") (name "/PCIE5_CLK_REQ_LS") (class "Default")
      (node (ref "IC15") (pin "10") (pinfunction "A8_10") (pintype "bidirectional"))
    )
    (net (code "101") (name "/PCIE5_COEX1") (class "Default")
      (node (ref "IC7") (pin "17") (pinfunction "B5_17") (pintype "bidirectional"))
    )
    (net (code "102") (name "/PCIE5_COEX1_LS") (class "Default")
      (node (ref "IC7") (pin "7") (pinfunction "A5_7") (pintype "bidirectional"))
    )
    (net (code "103") (name "/PCIE5_COEX2") (class "Default")
      (node (ref "IC15") (pin "19") (pinfunction "B3_19") (pintype "bidirectional"))
    )
    (net (code "104") (name "/PCIE5_COEX2_LS") (class "Default")
      (node (ref "IC15") (pin "5") (pinfunction "A3_5") (pintype "bidirectional"))
    )
    (net (code "105") (name "/PCIE5_LED_WLAN") (class "Default")
      (node (ref "IC7") (pin "21") (pinfunction "B1_21") (pintype "bidirectional"))
    )
    (net (code "106") (name "/PCIE5_LED_WLAN_LS") (class "Default")
      (node (ref "IC7") (pin "3") (pinfunction "A1_3") (pintype "bidirectional"))
    )
    (net (code "107") (name "/PCIE5_LED_WPAN") (class "Default")
      (node (ref "IC15") (pin "20") (pinfunction "B2_20") (pintype "bidirectional"))
    )
    (net (code "108") (name "/PCIE5_LED_WPAN_LS") (class "Default")
      (node (ref "IC15") (pin "4") (pinfunction "A2_4") (pintype "bidirectional"))
    )
    (net (code "109") (name "/PCIE5_LED_WWAN") (class "Default")
      (node (ref "IC7") (pin "14") (pinfunction "B8_14") (pintype "bidirectional"))
    )
    (net (code "110") (name "/PCIE5_LED_WWAN_LS") (class "Default")
      (node (ref "IC7") (pin "10") (pinfunction "A8_10") (pintype "bidirectional"))
    )
    (net (code "111") (name "/PCIE5_PERST") (class "Default")
      (node (ref "IC7") (pin "15") (pinfunction "B7_15") (pintype "bidirectional"))
    )
    (net (code "112") (name "/PCIE5_PERST_LS") (class "Default")
      (node (ref "IC7") (pin "9") (pinfunction "A7_9") (pintype "bidirectional"))
    )
    (net (code "113") (name "/PCIE5_UIM8") (class "Default")
      (node (ref "IC15") (pin "15") (pinfunction "B7_15") (pintype "bidirectional"))
    )
    (net (code "114") (name "/PCIE5_UIM8_LS") (class "Default")
      (node (ref "IC15") (pin "9") (pinfunction "A7_9") (pintype "bidirectional"))
    )
    (net (code "115") (name "/PCIE5_W_DISABLE") (class "Default")
      (node (ref "IC7") (pin "16") (pinfunction "B6_16") (pintype "bidirectional"))
    )
    (net (code "116") (name "/PCIE5_W_DISABLE_LS") (class "Default")
      (node (ref "IC7") (pin "8") (pinfunction "A6_8") (pintype "bidirectional"))
    )
    (net (code "117") (name "/PCIE6_CLK_REQ") (class "Default")
      (node (ref "IC15") (pin "18") (pinfunction "B4_18") (pintype "bidirectional"))
      (node (ref "R57") (pin "1") (pinfunction "1_1") (pintype "passive"))
    )
    (net (code "118") (name "/PCIE6_CLK_REQ_LS") (class "Default")
      (node (ref "IC15") (pin "6") (pinfunction "A4_6") (pintype "bidirectional"))
    )
    (net (code "119") (name "/PCIE6_COEX1") (class "Default")
      (node (ref "IC8") (pin "17") (pinfunction "B5_17") (pintype "bidirectional"))
    )
    (net (code "120") (name "/PCIE6_COEX1_LS") (class "Default")
      (node (ref "IC8") (pin "7") (pinfunction "A5_7") (pintype "bidirectional"))
    )
    (net (code "121") (name "/PCIE6_COEX2") (class "Default")
      (node (ref "IC15") (pin "21") (pinfunction "B1_21") (pintype "bidirectional"))
    )
    (net (code "122") (name "/PCIE6_COEX2_LS") (class "Default")
      (node (ref "IC15") (pin "3") (pinfunction "A1_3") (pintype "bidirectional"))
    )
    (net (code "123") (name "/PCIE6_LED_WLAN") (class "Default")
      (node (ref "IC8") (pin "14") (pinfunction "B8_14") (pintype "bidirectional"))
    )
    (net (code "124") (name "/PCIE6_LED_WLAN_LS") (class "Default")
      (node (ref "IC8") (pin "10") (pinfunction "A8_10") (pintype "bidirectional"))
    )
    (net (code "125") (name "/PCIE6_LED_WPAN") (class "Default")
      (node (ref "IC15") (pin "16") (pinfunction "B6_16") (pintype "bidirectional"))
    )
    (net (code "126") (name "/PCIE6_LED_WPAN_LS") (class "Default")
      (node (ref "IC15") (pin "8") (pinfunction "A6_8") (pintype "bidirectional"))
    )
    (net (code "127") (name "/PCIE6_LED_WWAN") (class "Default")
      (node (ref "IC8") (pin "19") (pinfunction "B3_19") (pintype "bidirectional"))
    )
    (net (code "128") (name "/PCIE6_LED_WWAN_LS") (class "Default")
      (node (ref "IC8") (pin "5") (pinfunction "A3_5") (pintype "bidirectional"))
    )
    (net (code "129") (name "/PCIE6_PERST") (class "Default")
      (node (ref "IC8") (pin "15") (pinfunction "B7_15") (pintype "bidirectional"))
    )
    (net (code "130") (name "/PCIE6_PERST_LS") (class "Default")
      (node (ref "IC8") (pin "9") (pinfunction "A7_9") (pintype "bidirectional"))
    )
    (net (code "131") (name "/PCIE6_UIM8") (class "Default")
      (node (ref "IC15") (pin "17") (pinfunction "B5_17") (pintype "bidirectional"))
    )
    (net (code "132") (name "/PCIE6_UIM8_LS") (class "Default")
      (node (ref "IC15") (pin "7") (pinfunction "A5_7") (pintype "bidirectional"))
    )
    (net (code "133") (name "/PCIE6_W_DISABLE") (class "Default")
      (node (ref "IC8") (pin "20") (pinfunction "B2_20") (pintype "bidirectional"))
    )
    (net (code "134") (name "/PCIE6_W_DISABLE_LS") (class "Default")
      (node (ref "IC8") (pin "4") (pinfunction "A2_4") (pintype "bidirectional"))
    )
    (net (code "135") (name "/PCIE7_CLK_REQ") (class "Default")
      (node (ref "IC17") (pin "15") (pinfunction "B7_15") (pintype "bidirectional"))
      (node (ref "R58") (pin "1") (pinfunction "1_1") (pintype "passive"))
    )
    (net (code "136") (name "/PCIE7_CLK_REQ_LS") (class "Default")
      (node (ref "IC17") (pin "9") (pinfunction "A7_9") (pintype "bidirectional"))
    )
    (net (code "137") (name "/PCIE7_COEX1") (class "Default")
      (node (ref "IC8") (pin "16") (pinfunction "B6_16") (pintype "bidirectional"))
    )
    (net (code "138") (name "/PCIE7_COEX1_LS") (class "Default")
      (node (ref "IC8") (pin "8") (pinfunction "A6_8") (pintype "bidirectional"))
    )
    (net (code "139") (name "/PCIE7_COEX2") (class "Default")
      (node (ref "IC17") (pin "16") (pinfunction "B6_16") (pintype "bidirectional"))
    )
    (net (code "140") (name "/PCIE7_COEX2_LS") (class "Default")
      (node (ref "IC17") (pin "8") (pinfunction "A6_8") (pintype "bidirectional"))
    )
    (net (code "141") (name "/PCIE7_LED_WLAN") (class "Default")
      (node (ref "IC16") (pin "21") (pinfunction "B1_21") (pintype "bidirectional"))
    )
    (net (code "142") (name "/PCIE7_LED_WLAN_LS") (class "Default")
      (node (ref "IC16") (pin "3") (pinfunction "A1_3") (pintype "bidirectional"))
    )
    (net (code "143") (name "/PCIE7_LED_WPAN") (class "Default")
      (node (ref "IC17") (pin "17") (pinfunction "B5_17") (pintype "bidirectional"))
    )
    (net (code "144") (name "/PCIE7_LED_WPAN_LS") (class "Default")
      (node (ref "IC17") (pin "7") (pinfunction "A5_7") (pintype "bidirectional"))
    )
    (net (code "145") (name "/PCIE7_LED_WWAN") (class "Default")
      (node (ref "IC16") (pin "17") (pinfunction "B5_17") (pintype "bidirectional"))
    )
    (net (code "146") (name "/PCIE7_LED_WWAN_LS") (class "Default")
      (node (ref "IC16") (pin "7") (pinfunction "A5_7") (pintype "bidirectional"))
    )
    (net (code "147") (name "/PCIE7_PERST") (class "Default")
      (node (ref "IC16") (pin "14") (pinfunction "B8_14") (pintype "bidirectional"))
    )
    (net (code "148") (name "/PCIE7_PERST_LS") (class "Default")
      (node (ref "IC16") (pin "10") (pinfunction "A8_10") (pintype "bidirectional"))
    )
    (net (code "149") (name "/PCIE7_UIM8") (class "Default")
      (node (ref "IC17") (pin "14") (pinfunction "B8_14") (pintype "bidirectional"))
    )
    (net (code "150") (name "/PCIE7_UIM8_LS") (class "Default")
      (node (ref "IC17") (pin "10") (pinfunction "A8_10") (pintype "bidirectional"))
    )
    (net (code "151") (name "/PCIE7_W_DISABLE") (class "Default")
      (node (ref "IC8") (pin "18") (pinfunction "B4_18") (pintype "bidirectional"))
    )
    (net (code "152") (name "/PCIE7_W_DISABLE_LS") (class "Default")
      (node (ref "IC8") (pin "6") (pinfunction "A4_6") (pintype "bidirectional"))
    )
    (net (code "153") (name "/PCIE8_CLK_REQ") (class "Default")
      (node (ref "IC17") (pin "18") (pinfunction "B4_18") (pintype "bidirectional"))
      (node (ref "R59") (pin "1") (pinfunction "1_1") (pintype "passive"))
    )
    (net (code "154") (name "/PCIE8_CLK_REQ_LS") (class "Default")
      (node (ref "IC17") (pin "6") (pinfunction "A4_6") (pintype "bidirectional"))
    )
    (net (code "155") (name "/PCIE8_COEX1") (class "Default")
      (node (ref "IC16") (pin "16") (pinfunction "B6_16") (pintype "bidirectional"))
    )
    (net (code "156") (name "/PCIE8_COEX1_LS") (class "Default")
      (node (ref "IC16") (pin "8") (pinfunction "A6_8") (pintype "bidirectional"))
    )
    (net (code "157") (name "/PCIE8_COEX2") (class "Default")
      (node (ref "IC17") (pin "19") (pinfunction "B3_19") (pintype "bidirectional"))
    )
    (net (code "158") (name "/PCIE8_COEX2_LS") (class "Default")
      (node (ref "IC17") (pin "5") (pinfunction "A3_5") (pintype "bidirectional"))
    )
    (net (code "159") (name "/PCIE8_LED_WLAN") (class "Default")
      (node (ref "IC12") (pin "16") (pinfunction "B6_16") (pintype "bidirectional"))
    )
    (net (code "160") (name "/PCIE8_LED_WLAN_LS") (class "Default")
      (node (ref "IC12") (pin "8") (pinfunction "A6_8") (pintype "bidirectional"))
    )
    (net (code "161") (name "/PCIE8_LED_WPAN") (class "Default")
      (node (ref "IC17") (pin "20") (pinfunction "B2_20") (pintype "bidirectional"))
    )
    (net (code "162") (name "/PCIE8_LED_WPAN_LS") (class "Default")
      (node (ref "IC17") (pin "4") (pinfunction "A2_4") (pintype "bidirectional"))
    )
    (net (code "163") (name "/PCIE8_LED_WWAN") (class "Default")
      (node (ref "IC16") (pin "20") (pinfunction "B2_20") (pintype "bidirectional"))
    )
    (net (code "164") (name "/PCIE8_LED_WWAN_LS") (class "Default")
      (node (ref "IC16") (pin "4") (pinfunction "A2_4") (pintype "bidirectional"))
    )
    (net (code "165") (name "/PCIE8_PERST") (class "Default")
      (node (ref "IC16") (pin "18") (pinfunction "B4_18") (pintype "bidirectional"))
    )
    (net (code "166") (name "/PCIE8_PERST_LS") (class "Default")
      (node (ref "IC16") (pin "6") (pinfunction "A4_6") (pintype "bidirectional"))
    )
    (net (code "167") (name "/PCIE8_UIM8") (class "Default")
      (node (ref "IC17") (pin "21") (pinfunction "B1_21") (pintype "bidirectional"))
    )
    (net (code "168") (name "/PCIE8_UIM8_LS") (class "Default")
      (node (ref "IC17") (pin "3") (pinfunction "A1_3") (pintype "bidirectional"))
    )
    (net (code "169") (name "/PCIE8_W_DISABLE") (class "Default")
      (node (ref "IC16") (pin "19") (pinfunction "B3_19") (pintype "bidirectional"))
    )
    (net (code "170") (name "/PCIE8_W_DISABLE_LS") (class "Default")
      (node (ref "IC16") (pin "5") (pinfunction "A3_5") (pintype "bidirectional"))
    )
    (net (code "171") (name "/PCIE_SMB_CLK") (class "Default")
      (node (ref "IC10") (pin "17") (pinfunction "B5_17") (pintype "bidirectional"))
    )
    (net (code "172") (name "/PCIE_SMB_CLK_LS") (class "Default")
      (node (ref "IC10") (pin "7") (pinfunction "A5_7") (pintype "bidirectional"))
    )
    (net (code "173") (name "/PCIE_SMB_DATA") (class "Default")
      (node (ref "IC16") (pin "15") (pinfunction "B7_15") (pintype "bidirectional"))
    )
    (net (code "174") (name "/PCIE_SMB_DATA_LS") (class "Default")
      (node (ref "IC16") (pin "9") (pinfunction "A7_9") (pintype "bidirectional"))
    )
    (net (code "175") (name "/STATUS_LED_G") (class "Default")
      (node (ref "IC12") (pin "15") (pinfunction "B7_15") (pintype "bidirectional"))
      (node (ref "R44") (pin "2") (pinfunction "2_2") (pintype "passive"))
    )
    (net (code "176") (name "/STATUS_LED_G_LS") (class "Default")
      (node (ref "IC12") (pin "9") (pinfunction "A7_9") (pintype "bidirectional"))
    )
    (net (code "177") (name "/STATUS_LED_R") (class "Default")
      (node (ref "IC12") (pin "14") (pinfunction "B8_14") (pintype "bidirectional"))
      (node (ref "R47") (pin "2") (pinfunction "2_2") (pintype "passive"))
    )
    (net (code "178") (name "/STATUS_LED_R_LS") (class "Default")
      (node (ref "IC12") (pin "10") (pinfunction "A8_10") (pintype "bidirectional"))
    )
    (net (code "179") (name "FMC_HPC_VADJ") (class "Default")
      (node (ref "C44") (pin "2") (pinfunction "2_2") (pintype "passive"))
      (node (ref "C45") (pin "2") (pinfunction "2_2") (pintype "passive"))
      (node (ref "C46") (pin "2") (pinfunction "2_2") (pintype "passive"))
      (node (ref "C47") (pin "2") (pinfunction "2_2") (pintype "passive"))
      (node (ref "C52") (pin "2") (pinfunction "2_2") (pintype "passive"))
      (node (ref "C53") (pin "2") (pinfunction "2_2") (pintype "passive"))
      (node (ref "C54") (pin "2") (pinfunction "2_2") (pintype "passive"))
      (node (ref "C58") (pin "2") (pinfunction "2_2") (pintype "passive"))
      (node (ref "C59") (pin "2") (pinfunction "2_2") (pintype "passive"))
      (node (ref "C64") (pin "2") (pinfunction "2_2") (pintype "passive"))
      (node (ref "C65") (pin "2") (pinfunction "2_2") (pintype "passive"))
      (node (ref "IC10") (pin "1") (pinfunction "VCCA_1") (pintype "power_in"))
      (node (ref "IC11") (pin "1") (pinfunction "VCCA_1") (pintype "power_in"))
      (node (ref "IC12") (pin "1") (pinfunction "VCCA_1") (pintype "power_in"))
      (node (ref "IC13") (pin "1") (pinfunction "VCCA_1") (pintype "power_in"))
      (node (ref "IC14") (pin "1") (pinfunction "VCCA_1") (pintype "power_in"))
      (node (ref "IC15") (pin "1") (pinfunction "VCCA_1") (pintype "power_in"))
      (node (ref "IC16") (pin "1") (pinfunction "VCCA_1") (pintype "power_in"))
      (node (ref "IC17") (pin "1") (pinfunction "VCCA_1") (pintype "power_in"))
      (node (ref "IC7") (pin "1") (pinfunction "VCCA_1") (pintype "power_in"))
      (node (ref "IC8") (pin "1") (pinfunction "VCCA_1") (pintype "power_in"))
      (node (ref "IC9") (pin "1") (pinfunction "VCCA_1") (pintype "power_in"))
      (node (ref "J27") (pin "11") (pinfunction "11_11") (pintype "passive"))
      (node (ref "R36") (pin "1") (pinfunction "1_1") (pintype "passive"))
      (node (ref "R37") (pin "1") (pinfunction "1_1") (pintype "passive"))
      (node (ref "R38") (pin "1") (pinfunction "1_1") (pintype "passive"))
      (node (ref "R39") (pin "1") (pinfunction "1_1") (pintype "passive"))
      (node (ref "R48") (pin "1") (pinfunction "1_1") (pintype "passive"))
      (node (ref "R49") (pin "1") (pinfunction "1_1") (pintype "passive"))
      (node (ref "R50") (pin "1") (pinfunction "1_1") (pintype "passive"))
      (node (ref "R60") (pin "1") (pinfunction "1_1") (pintype "passive"))
      (node (ref "R62") (pin "1") (pinfunction "1_1") (pintype "passive"))
      (node (ref "R63") (pin "1") (pinfunction "1_1") (pintype "passive"))
      (node (ref "R66") (pin "1") (pinfunction "1_1") (pintype "passive"))
      (node (ref "R69") (pin "1") (pinfunction "1_1") (pintype "passive"))
      (node (ref "R70") (pin "1") (pinfunction "1_1") (pintype "passive"))
      (node (ref "VT1") (pin "G") (pinfunction "G_G") (pintype "passive"))
      (node (ref "VT2") (pin "G") (pinfunction "G_G") (pintype "passive"))
    )
    (net (code "180") (name "GND") (class "Default")
      (node (ref "C44") (pin "1") (pinfunction "1_1") (pintype "passive"))
      (node (ref "C45") (pin "1") (pinfunction "1_1") (pintype "passive"))
      (node (ref "C46") (pin "1") (pinfunction "1_1") (pintype "passive"))
      (node (ref "C47") (pin "1") (pinfunction "1_1") (pintype "passive"))
      (node (ref "C48") (pin "1") (pinfunction "1_1") (pintype "passive"))
      (node (ref "C49") (pin "1") (pinfunction "1_1") (pintype "passive"))
      (node (ref "C50") (pin "1") (pinfunction "1_1") (pintype "passive"))
      (node (ref "C51") (pin "1") (pinfunction "1_1") (pintype "passive"))
      (node (ref "C52") (pin "1") (pinfunction "1_1") (pintype "passive"))
      (node (ref "C53") (pin "1") (pinfunction "1_1") (pintype "passive"))
      (node (ref "C54") (pin "1") (pinfunction "1_1") (pintype "passive"))
      (node (ref "C55") (pin "1") (pinfunction "1_1") (pintype "passive"))
      (node (ref "C56") (pin "1") (pinfunction "1_1") (pintype "passive"))
      (node (ref "C57") (pin "1") (pinfunction "1_1") (pintype "passive"))
      (node (ref "C58") (pin "1") (pinfunction "1_1") (pintype "passive"))
      (node (ref "C59") (pin "1") (pinfunction "1_1") (pintype "passive"))
      (node (ref "C60") (pin "1") (pinfunction "1_1") (pintype "passive"))
      (node (ref "C61") (pin "1") (pinfunction "1_1") (pintype "passive"))
      (node (ref "C64") (pin "1") (pinfunction "1_1") (pintype "passive"))
      (node (ref "C65") (pin "1") (pinfunction "1_1") (pintype "passive"))
      (node (ref "C66") (pin "1") (pinfunction "1_1") (pintype "passive"))
      (node (ref "C67") (pin "1") (pinfunction "1_1") (pintype "passive"))
      (node (ref "IC10") (pin "11") (pinfunction "GND_11") (pintype "passive"))
      (node (ref "IC10") (pin "12") (pinfunction "GND_12") (pintype "passive"))
      (node (ref "IC10") (pin "13") (pinfunction "GND_13") (pintype "passive"))
      (node (ref "IC10") (pin "22") (pinfunction "~{OE}_22") (pintype "input"))
      (node (ref "IC10") (pin "PAD") (pinfunction "GND_PAD") (pintype "passive"))
      (node (ref "IC11") (pin "11") (pinfunction "GND_11") (pintype "passive"))
      (node (ref "IC11") (pin "12") (pinfunction "GND_12") (pintype "passive"))
      (node (ref "IC11") (pin "13") (pinfunction "GND_13") (pintype "passive"))
      (node (ref "IC11") (pin "22") (pinfunction "~{OE}_22") (pintype "input"))
      (node (ref "IC11") (pin "PAD") (pinfunction "GND_PAD") (pintype "passive"))
      (node (ref "IC12") (pin "11") (pinfunction "GND_11") (pintype "passive"))
      (node (ref "IC12") (pin "12") (pinfunction "GND_12") (pintype "passive"))
      (node (ref "IC12") (pin "13") (pinfunction "GND_13") (pintype "passive"))
      (node (ref "IC12") (pin "22") (pinfunction "~{OE}_22") (pintype "input"))
      (node (ref "IC12") (pin "PAD") (pinfunction "GND_PAD") (pintype "passive"))
      (node (ref "IC13") (pin "11") (pinfunction "GND_11") (pintype "passive"))
      (node (ref "IC13") (pin "12") (pinfunction "GND_12") (pintype "passive"))
      (node (ref "IC13") (pin "13") (pinfunction "GND_13") (pintype "passive"))
      (node (ref "IC13") (pin "22") (pinfunction "~{OE}_22") (pintype "input"))
      (node (ref "IC13") (pin "PAD") (pinfunction "GND_PAD") (pintype "passive"))
      (node (ref "IC14") (pin "11") (pinfunction "GND_11") (pintype "passive"))
      (node (ref "IC14") (pin "12") (pinfunction "GND_12") (pintype "passive"))
      (node (ref "IC14") (pin "13") (pinfunction "GND_13") (pintype "passive"))
      (node (ref "IC14") (pin "22") (pinfunction "~{OE}_22") (pintype "input"))
      (node (ref "IC14") (pin "PAD") (pinfunction "GND_PAD") (pintype "passive"))
      (node (ref "IC15") (pin "11") (pinfunction "GND_11") (pintype "passive"))
      (node (ref "IC15") (pin "12") (pinfunction "GND_12") (pintype "passive"))
      (node (ref "IC15") (pin "13") (pinfunction "GND_13") (pintype "passive"))
      (node (ref "IC15") (pin "22") (pinfunction "~{OE}_22") (pintype "input"))
      (node (ref "IC15") (pin "PAD") (pinfunction "GND_PAD") (pintype "passive"))
      (node (ref "IC16") (pin "11") (pinfunction "GND_11") (pintype "passive"))
      (node (ref "IC16") (pin "12") (pinfunction "GND_12") (pintype "passive"))
      (node (ref "IC16") (pin "13") (pinfunction "GND_13") (pintype "passive"))
      (node (ref "IC16") (pin "22") (pinfunction "~{OE}_22") (pintype "input"))
      (node (ref "IC16") (pin "PAD") (pinfunction "GND_PAD") (pintype "passive"))
      (node (ref "IC17") (pin "11") (pinfunction "GND_11") (pintype "passive"))
      (node (ref "IC17") (pin "12") (pinfunction "GND_12") (pintype "passive"))
      (node (ref "IC17") (pin "13") (pinfunction "GND_13") (pintype "passive"))
      (node (ref "IC17") (pin "22") (pinfunction "~{OE}_22") (pintype "input"))
      (node (ref "IC17") (pin "PAD") (pinfunction "GND_PAD") (pintype "passive"))
      (node (ref "IC7") (pin "11") (pinfunction "GND_11") (pintype "passive"))
      (node (ref "IC7") (pin "12") (pinfunction "GND_12") (pintype "passive"))
      (node (ref "IC7") (pin "13") (pinfunction "GND_13") (pintype "passive"))
      (node (ref "IC7") (pin "22") (pinfunction "~{OE}_22") (pintype "input"))
      (node (ref "IC7") (pin "PAD") (pinfunction "GND_PAD") (pintype "passive"))
      (node (ref "IC8") (pin "11") (pinfunction "GND_11") (pintype "passive"))
      (node (ref "IC8") (pin "12") (pinfunction "GND_12") (pintype "passive"))
      (node (ref "IC8") (pin "13") (pinfunction "GND_13") (pintype "passive"))
      (node (ref "IC8") (pin "22") (pinfunction "~{OE}_22") (pintype "input"))
      (node (ref "IC8") (pin "PAD") (pinfunction "GND_PAD") (pintype "passive"))
      (node (ref "IC9") (pin "11") (pinfunction "GND_11") (pintype "passive"))
      (node (ref "IC9") (pin "12") (pinfunction "GND_12") (pintype "passive"))
      (node (ref "IC9") (pin "13") (pinfunction "GND_13") (pintype "passive"))
      (node (ref "IC9") (pin "22") (pinfunction "~{OE}_22") (pintype "input"))
      (node (ref "IC9") (pin "PAD") (pinfunction "GND_PAD") (pintype "passive"))
      (node (ref "J27") (pin "13") (pinfunction "13_13") (pintype "passive"))
      (node (ref "J27") (pin "14") (pinfunction "14_14") (pintype "passive"))
      (node (ref "R40") (pin "1") (pinfunction "1_1") (pintype "passive"))
      (node (ref "R41") (pin "1") (pinfunction "1_1") (pintype "passive"))
      (node (ref "R42") (pin "1") (pinfunction "1_1") (pintype "passive"))
      (node (ref "R43") (pin "1") (pinfunction "1_1") (pintype "passive"))
      (node (ref "R51") (pin "1") (pinfunction "1_1") (pintype "passive"))
      (node (ref "R52") (pin "1") (pinfunction "1_1") (pintype "passive"))
      (node (ref "R53") (pin "1") (pinfunction "1_1") (pintype "passive"))
      (node (ref "R64") (pin "1") (pinfunction "1_1") (pintype "passive"))
      (node (ref "R65") (pin "1") (pinfunction "1_1") (pintype "passive"))
      (node (ref "R72") (pin "1") (pinfunction "1_1") (pintype "passive"))
      (node (ref "R73") (pin "1") (pinfunction "1_1") (pintype "passive"))
      (node (ref "R75") (pin "1") (pinfunction "1_1") (pintype "passive"))
      (node (ref "VT3") (pin "S") (pinfunction "S_S") (pintype "passive"))
    )
    (net (code "181") (name "Net-(C62-Pad1)") (class "Default")
      (node (ref "C62") (pin "1") (pinfunction "1_1") (pintype "passive"))
      (node (ref "C63") (pin "1") (pinfunction "1_1") (pintype "passive"))
      (node (ref "J28") (pin "2") (pinfunction "2_2") (pintype "passive"))
      (node (ref "J29") (pin "2") (pinfunction "2_2") (pintype "passive"))
      (node (ref "R68") (pin "2") (pinfunction "2_2") (pintype "passive"))
      (node (ref "R71") (pin "2") (pinfunction "2_2") (pintype "passive"))
      (node (ref "R74") (pin "2") (pinfunction "2_2") (pintype "passive"))
    )
    (net (code "182") (name "Net-(C62-Pad2)") (class "Default")
      (node (ref "C62") (pin "2") (pinfunction "2_2") (pintype "passive"))
      (node (ref "C63") (pin "2") (pinfunction "2_2") (pintype "passive"))
      (node (ref "J28") (pin "1") (pinfunction "1_1") (pintype "passive"))
      (node (ref "J29") (pin "1") (pinfunction "1_1") (pintype "passive"))
      (node (ref "R75") (pin "2") (pinfunction "2_2") (pintype "passive"))
      (node (ref "VT3") (pin "D") (pinfunction "D_D") (pintype "passive"))
    )
    (net (code "183") (name "Net-(IC7-DIR)") (class "Default")
      (node (ref "IC7") (pin "2") (pinfunction "DIR_2") (pintype "input"))
      (node (ref "R36") (pin "2") (pinfunction "2_2") (pintype "passive"))
      (node (ref "R40") (pin "2") (pinfunction "2_2") (pintype "passive"))
    )
    (net (code "184") (name "Net-(IC8-DIR)") (class "Default")
      (node (ref "IC8") (pin "2") (pinfunction "DIR_2") (pintype "input"))
      (node (ref "R37") (pin "2") (pinfunction "2_2") (pintype "passive"))
      (node (ref "R41") (pin "2") (pinfunction "2_2") (pintype "passive"))
    )
    (net (code "185") (name "Net-(IC9-DIR)") (class "Default")
      (node (ref "IC9") (pin "2") (pinfunction "DIR_2") (pintype "input"))
      (node (ref "R38") (pin "2") (pinfunction "2_2") (pintype "passive"))
      (node (ref "R42") (pin "2") (pinfunction "2_2") (pintype "passive"))
    )
    (net (code "186") (name "Net-(IC10-DIR)") (class "Default")
      (node (ref "IC10") (pin "2") (pinfunction "DIR_2") (pintype "input"))
      (node (ref "R39") (pin "2") (pinfunction "2_2") (pintype "passive"))
      (node (ref "R43") (pin "2") (pinfunction "2_2") (pintype "passive"))
    )
    (net (code "187") (name "Net-(IC11-DIR)") (class "Default")
      (node (ref "IC11") (pin "2") (pinfunction "DIR_2") (pintype "input"))
      (node (ref "R48") (pin "2") (pinfunction "2_2") (pintype "passive"))
      (node (ref "R51") (pin "2") (pinfunction "2_2") (pintype "passive"))
    )
    (net (code "188") (name "Net-(IC12-DIR)") (class "Default")
      (node (ref "IC12") (pin "2") (pinfunction "DIR_2") (pintype "input"))
      (node (ref "R49") (pin "2") (pinfunction "2_2") (pintype "passive"))
      (node (ref "R52") (pin "2") (pinfunction "2_2") (pintype "passive"))
    )
    (net (code "189") (name "Net-(IC13-DIR)") (class "Default")
      (node (ref "IC13") (pin "2") (pinfunction "DIR_2") (pintype "input"))
      (node (ref "R50") (pin "2") (pinfunction "2_2") (pintype "passive"))
      (node (ref "R53") (pin "2") (pinfunction "2_2") (pintype "passive"))
    )
    (net (code "190") (name "Net-(IC14-DIR)") (class "Default")
      (node (ref "IC14") (pin "2") (pinfunction "DIR_2") (pintype "input"))
      (node (ref "R62") (pin "2") (pinfunction "2_2") (pintype "passive"))
      (node (ref "R64") (pin "2") (pinfunction "2_2") (pintype "passive"))
    )
    (net (code "191") (name "Net-(IC15-DIR)") (class "Default")
      (node (ref "IC15") (pin "2") (pinfunction "DIR_2") (pintype "input"))
      (node (ref "R63") (pin "2") (pinfunction "2_2") (pintype "passive"))
      (node (ref "R65") (pin "2") (pinfunction "2_2") (pintype "passive"))
    )
    (net (code "192") (name "Net-(IC16-DIR)") (class "Default")
      (node (ref "IC16") (pin "2") (pinfunction "DIR_2") (pintype "input"))
      (node (ref "R69") (pin "2") (pinfunction "2_2") (pintype "passive"))
      (node (ref "R72") (pin "2") (pinfunction "2_2") (pintype "passive"))
    )
    (net (code "193") (name "Net-(IC17-DIR)") (class "Default")
      (node (ref "IC17") (pin "2") (pinfunction "DIR_2") (pintype "input"))
      (node (ref "R70") (pin "2") (pinfunction "2_2") (pintype "passive"))
      (node (ref "R73") (pin "2") (pinfunction "2_2") (pintype "passive"))
    )
    (net (code "194") (name "Net-(LED9-Pad3)") (class "Default")
      (node (ref "LED9") (pin "3") (pinfunction "3_3") (pintype "power_in"))
      (node (ref "R44") (pin "1") (pinfunction "1_1") (pintype "passive"))
    )
    (net (code "195") (name "Net-(LED9-Pad4)") (class "Default")
      (node (ref "LED9") (pin "4") (pinfunction "4_4") (pintype "power_in"))
      (node (ref "R47") (pin "1") (pinfunction "1_1") (pintype "passive"))
    )
    (net (code "196") (name "Net-(R76-Pad2)") (class "Default")
      (node (ref "R76") (pin "2") (pinfunction "2_2") (pintype "passive"))
      (node (ref "VT3") (pin "G") (pinfunction "G_G") (pintype "passive"))
    )
    (net (code "197") (name "VCC3P3_1") (class "Default")
      (node (ref "C48") (pin "2") (pinfunction "2_2") (pintype "passive"))
      (node (ref "C49") (pin "2") (pinfunction "2_2") (pintype "passive"))
      (node (ref "C50") (pin "2") (pinfunction "2_2") (pintype "passive"))
      (node (ref "C51") (pin "2") (pinfunction "2_2") (pintype "passive"))
      (node (ref "C55") (pin "2") (pinfunction "2_2") (pintype "passive"))
      (node (ref "C56") (pin "2") (pinfunction "2_2") (pintype "passive"))
      (node (ref "C57") (pin "2") (pinfunction "2_2") (pintype "passive"))
      (node (ref "C60") (pin "2") (pinfunction "2_2") (pintype "passive"))
      (node (ref "C61") (pin "2") (pinfunction "2_2") (pintype "passive"))
      (node (ref "C66") (pin "2") (pinfunction "2_2") (pintype "passive"))
      (node (ref "C67") (pin "2") (pinfunction "2_2") (pintype "passive"))
      (node (ref "IC10") (pin "23") (pinfunction "VCCB_23") (pintype "power_in"))
      (node (ref "IC10") (pin "24") (pinfunction "VCCB_24") (pintype "power_in"))
      (node (ref "IC11") (pin "23") (pinfunction "VCCB_23") (pintype "power_in"))
      (node (ref "IC11") (pin "24") (pinfunction "VCCB_24") (pintype "power_in"))
      (node (ref "IC12") (pin "23") (pinfunction "VCCB_23") (pintype "power_in"))
      (node (ref "IC12") (pin "24") (pinfunction "VCCB_24") (pintype "power_in"))
      (node (ref "IC13") (pin "23") (pinfunction "VCCB_23") (pintype "power_in"))
      (node (ref "IC13") (pin "24") (pinfunction "VCCB_24") (pintype "power_in"))
      (node (ref "IC14") (pin "23") (pinfunction "VCCB_23") (pintype "power_in"))
      (node (ref "IC14") (pin "24") (pinfunction "VCCB_24") (pintype "power_in"))
      (node (ref "IC15") (pin "23") (pinfunction "VCCB_23") (pintype "power_in"))
      (node (ref "IC15") (pin "24") (pinfunction "VCCB_24") (pintype "power_in"))
      (node (ref "IC16") (pin "23") (pinfunction "VCCB_23") (pintype "power_in"))
      (node (ref "IC16") (pin "24") (pinfunction "VCCB_24") (pintype "power_in"))
      (node (ref "IC17") (pin "23") (pinfunction "VCCB_23") (pintype "power_in"))
      (node (ref "IC17") (pin "24") (pinfunction "VCCB_24") (pintype "power_in"))
      (node (ref "IC7") (pin "23") (pinfunction "VCCB_23") (pintype "power_in"))
      (node (ref "IC7") (pin "24") (pinfunction "VCCB_24") (pintype "power_in"))
      (node (ref "IC8") (pin "23") (pinfunction "VCCB_23") (pintype "power_in"))
      (node (ref "IC8") (pin "24") (pinfunction "VCCB_24") (pintype "power_in"))
      (node (ref "IC9") (pin "23") (pinfunction "VCCB_23") (pintype "power_in"))
      (node (ref "IC9") (pin "24") (pinfunction "VCCB_24") (pintype "power_in"))
      (node (ref "J27") (pin "12") (pinfunction "12_12") (pintype "passive"))
      (node (ref "LED9") (pin "1") (pinfunction "1_1") (pintype "power_in"))
      (node (ref "LED9") (pin "2") (pinfunction "2_2") (pintype "power_in"))
      (node (ref "R45") (pin "2") (pinfunction "2_2") (pintype "passive"))
      (node (ref "R46") (pin "2") (pinfunction "2_2") (pintype "passive"))
      (node (ref "R54") (pin "2") (pinfunction "2_2") (pintype "passive"))
      (node (ref "R55") (pin "2") (pinfunction "2_2") (pintype "passive"))
      (node (ref "R56") (pin "2") (pinfunction "2_2") (pintype "passive"))
      (node (ref "R57") (pin "2") (pinfunction "2_2") (pintype "passive"))
      (node (ref "R58") (pin "2") (pinfunction "2_2") (pintype "passive"))
      (node (ref "R59") (pin "2") (pinfunction "2_2") (pintype "passive"))
      (node (ref "R61") (pin "1") (pinfunction "1_1") (pintype "passive"))
      (node (ref "R67") (pin "1") (pinfunction "1_1") (pintype "passive"))
    )
    (net (code "198") (name "VCC3P3_2") (class "Default")
      (node (ref "R74") (pin "1") (pinfunction "1_1") (pintype "passive"))
    )
    (net (code "199") (name "VCC5P0") (class "Default")
      (node (ref "R71") (pin "1") (pinfunction "1_1") (pintype "passive"))
    )
    (net (code "200") (name "VCC_INT") (class "Default")
      (node (ref "R68") (pin "1") (pinfunction "1_1") (pintype "passive"))
    )
    (net (code "201") (name "unconnected-(IC10-A1-Pad3)") (class "Default")
      (node (ref "IC10") (pin "3") (pinfunction "A1_3") (pintype "bidirectional+no_connect"))
    )
    (net (code "202") (name "unconnected-(IC10-A2-Pad4)") (class "Default")
      (node (ref "IC10") (pin "4") (pinfunction "A2_4") (pintype "bidirectional+no_connect"))
    )
    (net (code "203") (name "unconnected-(IC10-A3-Pad5)") (class "Default")
      (node (ref "IC10") (pin "5") (pinfunction "A3_5") (pintype "bidirectional+no_connect"))
    )
    (net (code "204") (name "unconnected-(IC10-A6-Pad8)") (class "Default")
      (node (ref "IC10") (pin "8") (pinfunction "A6_8") (pintype "bidirectional+no_connect"))
    )
    (net (code "205") (name "unconnected-(IC10-A7-Pad9)") (class "Default")
      (node (ref "IC10") (pin "9") (pinfunction "A7_9") (pintype "bidirectional+no_connect"))
    )
    (net (code "206") (name "unconnected-(IC10-A8-Pad10)") (class "Default")
      (node (ref "IC10") (pin "10") (pinfunction "A8_10") (pintype "bidirectional+no_connect"))
    )
    (net (code "207") (name "unconnected-(IC10-B1-Pad21)") (class "Default")
      (node (ref "IC10") (pin "21") (pinfunction "B1_21") (pintype "bidirectional+no_connect"))
    )
    (net (code "208") (name "unconnected-(IC10-B2-Pad20)") (class "Default")
      (node (ref "IC10") (pin "20") (pinfunction "B2_20") (pintype "bidirectional+no_connect"))
    )
    (net (code "209") (name "unconnected-(IC10-B3-Pad19)") (class "Default")
      (node (ref "IC10") (pin "19") (pinfunction "B3_19") (pintype "bidirectional+no_connect"))
    )
    (net (code "210") (name "unconnected-(IC10-B6-Pad16)") (class "Default")
      (node (ref "IC10") (pin "16") (pinfunction "B6_16") (pintype "bidirectional+no_connect"))
    )
    (net (code "211") (name "unconnected-(IC10-B7-Pad15)") (class "Default")
      (node (ref "IC10") (pin "15") (pinfunction "B7_15") (pintype "bidirectional+no_connect"))
    )
    (net (code "212") (name "unconnected-(IC10-B8-Pad14)") (class "Default")
      (node (ref "IC10") (pin "14") (pinfunction "B8_14") (pintype "bidirectional+no_connect"))
    )
  )
)
